# SCH_YDS-Charger-Daughter-Board_2022-05-2.net
KiCad netlist of a schematic drawn in EasyEDA
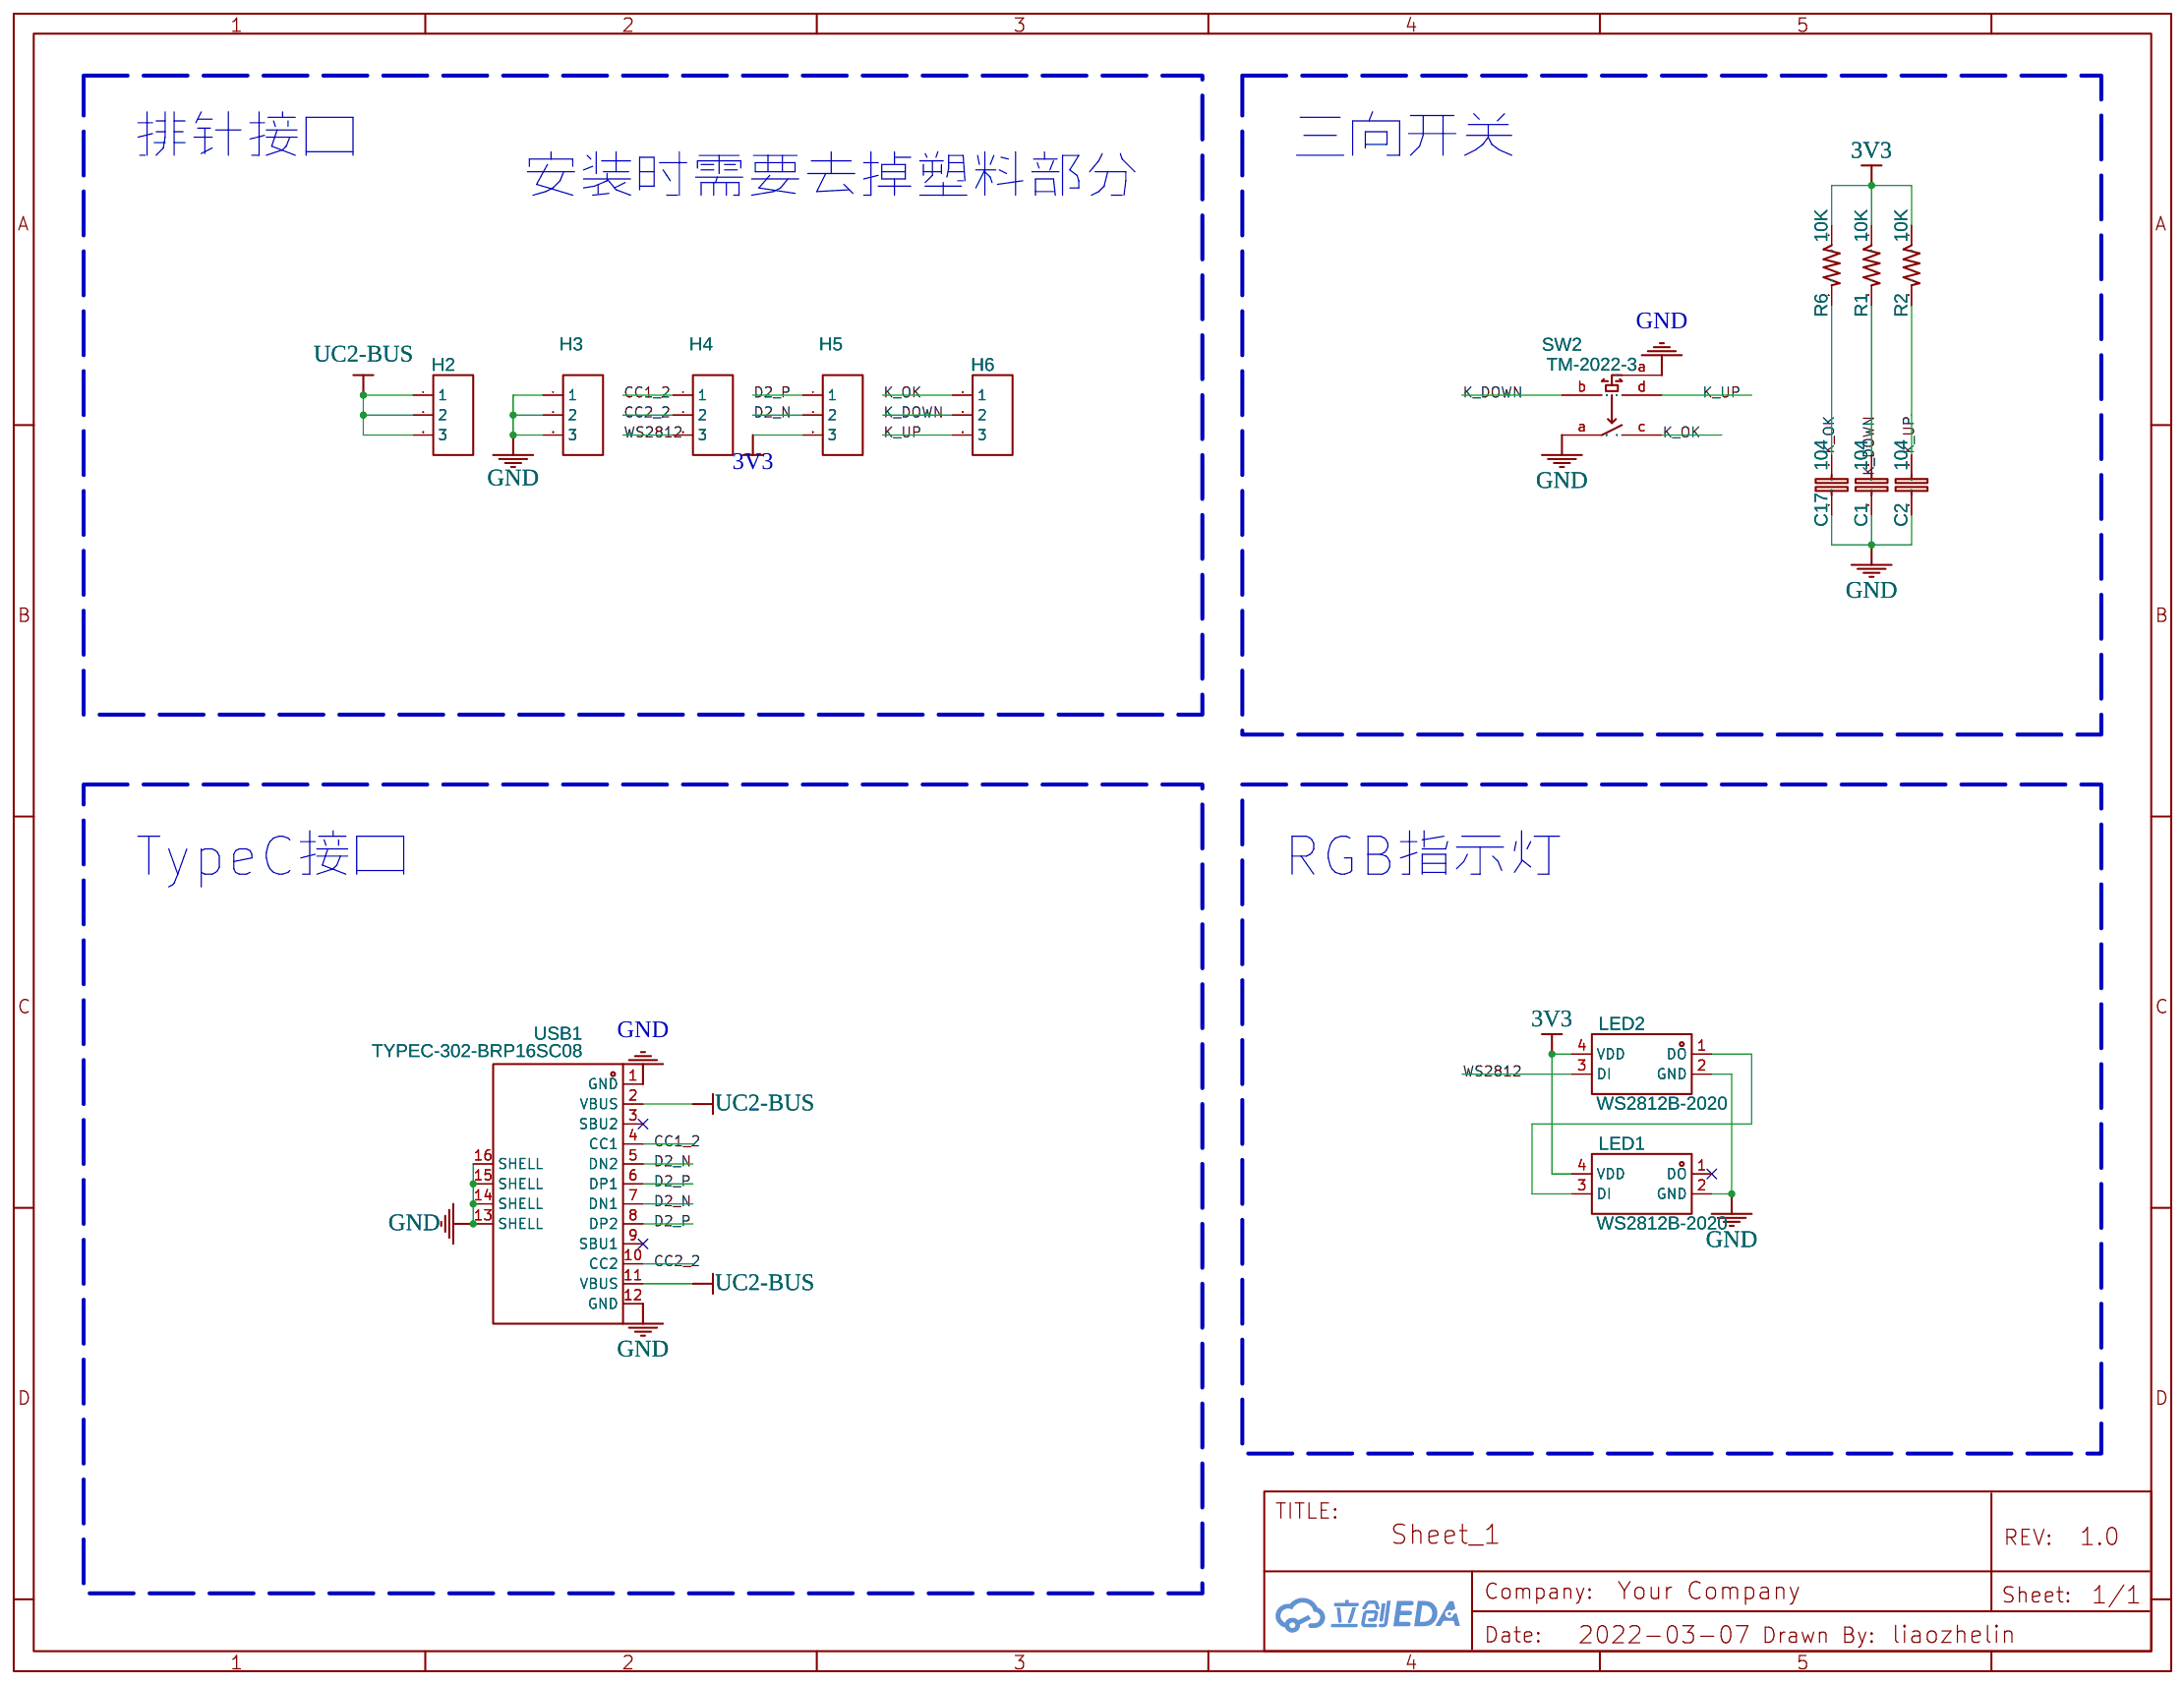
[diagram p0: schematic sheet]

(export (version "E")
  (design (tool "Eeschema 10.0.6"))
  (components
    (comp (ref "C1") (value "104") (libsource (lib "") (part "1.0PF-50V(-_+.25PF)(0603)")))
    (comp (ref "C2") (value "104") (libsource (lib "") (part "1.0PF-50V(-_+.25PF)(0603)")))
    (comp (ref "C17") (value "104") (libsource (lib "") (part "1.0PF-50V(-_+.25PF)(0603)")))
    (comp (ref "H2")
      (value "HDR-F-2.54_1x3")
      (fields (field (name "BOM_Supplier Part") "C146690"))
      (libsource (lib "") (part "HDR-F-2.54_1x3"))
    )
    (comp (ref "H3")
      (value "HDR-F-2.54_1x3")
      (fields (field (name "BOM_Supplier Part") "C146690"))
      (libsource (lib "") (part "HDR-F-2.54_1x3"))
    )
    (comp (ref "H4")
      (value "HDR-F-2.54_1x3")
      (fields (field (name "BOM_Supplier Part") "C146690"))
      (libsource (lib "") (part "HDR-F-2.54_1x3"))
    )
    (comp (ref "H5")
      (value "HDR-F-2.54_1x3")
      (fields (field (name "BOM_Supplier Part") "C146690"))
      (libsource (lib "") (part "HDR-F-2.54_1x3"))
    )
    (comp (ref "H6")
      (value "HDR-F-2.54_1x3")
      (fields (field (name "BOM_Supplier Part") "C146690"))
      (libsource (lib "") (part "HDR-F-2.54_1x3"))
    )
    (comp (ref "LED1")
      (value "WS2812B-2020")
      (fields (field (name "BOM_Supplier Part") "C965555"))
      (libsource (lib "") (part "WS2812B-2020"))
    )
    (comp (ref "LED2")
      (value "WS2812B-2020")
      (fields (field (name "BOM_Supplier Part") "C965555"))
      (libsource (lib "") (part "WS2812B-2020"))
    )
    (comp (ref "R1") (value "10K") (libsource (lib "") (part "1.2MOHMS-1_10W-1%(0603)")))
    (comp (ref "R2") (value "10K") (libsource (lib "") (part "1.2MOHMS-1_10W-1%(0603)")))
    (comp (ref "R6") (value "10K") (libsource (lib "") (part "1.2MOHMS-1_10W-1%(0603)")))
    (comp (ref "SW2")
      (value "TM-2022-3")
      (fields (field (name "BOM_Supplier Part") "C318952"))
      (libsource (lib "") (part "TM-2022-3"))
    )
    (comp (ref "USB1")
      (value "TYPEC-302-BRP16SC08")
      (fields (field (name "BOM_Supplier Part") "C2835312"))
      (libsource (lib "") (part "TYPEC-302-BRP16SC08"))
    )
  )
  (nets
    (net (code "1") (name "/CC1_2") (class "Default")
      (node (ref "H4") (pin "1") (pinfunction "1_1") (pintype "input"))
      (node (ref "USB1") (pin "4") (pinfunction "CC1_4") (pintype "unspecified"))
    )
    (net (code "2") (name "/CC2_2") (class "Default")
      (node (ref "H4") (pin "2") (pinfunction "2_2") (pintype "input"))
      (node (ref "USB1") (pin "10") (pinfunction "CC2_10") (pintype "unspecified"))
    )
    (net (code "3") (name "/D2_N") (class "Default")
      (node (ref "H5") (pin "2") (pinfunction "2_2") (pintype "input"))
      (node (ref "USB1") (pin "5") (pinfunction "DN2_5") (pintype "unspecified"))
      (node (ref "USB1") (pin "7") (pinfunction "DN1_7") (pintype "unspecified"))
    )
    (net (code "4") (name "/D2_P") (class "Default")
      (node (ref "H5") (pin "1") (pinfunction "1_1") (pintype "input"))
      (node (ref "USB1") (pin "6") (pinfunction "DP1_6") (pintype "unspecified"))
      (node (ref "USB1") (pin "8") (pinfunction "DP2_8") (pintype "unspecified"))
    )
    (net (code "5") (name "/K_DOWN") (class "Default")
      (node (ref "C1") (pin "1") (pinfunction "1_1") (pintype "unspecified"))
      (node (ref "H6") (pin "2") (pinfunction "2_2") (pintype "input"))
      (node (ref "R1") (pin "2") (pinfunction "2_2") (pintype "unspecified"))
      (node (ref "SW2") (pin "b") (pinfunction "b_b") (pintype "unspecified"))
    )
    (net (code "6") (name "/K_OK") (class "Default")
      (node (ref "C17") (pin "1") (pinfunction "1_1") (pintype "unspecified"))
      (node (ref "H6") (pin "1") (pinfunction "1_1") (pintype "input"))
      (node (ref "R6") (pin "2") (pinfunction "2_2") (pintype "unspecified"))
      (node (ref "SW2") (pin "c") (pinfunction "c_c") (pintype "unspecified"))
    )
    (net (code "7") (name "/K_UP") (class "Default")
      (node (ref "C2") (pin "1") (pinfunction "1_1") (pintype "unspecified"))
      (node (ref "H6") (pin "3") (pinfunction "3_3") (pintype "input"))
      (node (ref "R2") (pin "2") (pinfunction "2_2") (pintype "unspecified"))
      (node (ref "SW2") (pin "d") (pinfunction "d_d") (pintype "unspecified"))
    )
    (net (code "8") (name "/WS2812") (class "Default")
      (node (ref "H4") (pin "3") (pinfunction "3_3") (pintype "input"))
      (node (ref "LED2") (pin "3") (pinfunction "DI_3") (pintype "unspecified"))
    )
    (net (code "9") (name "3V3") (class "Default")
      (node (ref "H5") (pin "3") (pinfunction "3_3") (pintype "input"))
      (node (ref "LED1") (pin "4") (pinfunction "VDD_4") (pintype "unspecified"))
      (node (ref "LED2") (pin "4") (pinfunction "VDD_4") (pintype "unspecified"))
      (node (ref "R1") (pin "1") (pinfunction "1_1") (pintype "unspecified"))
      (node (ref "R2") (pin "1") (pinfunction "1_1") (pintype "unspecified"))
      (node (ref "R6") (pin "1") (pinfunction "1_1") (pintype "unspecified"))
    )
    (net (code "10") (name "GND") (class "Default")
      (node (ref "C1") (pin "2") (pinfunction "2_2") (pintype "unspecified"))
      (node (ref "C17") (pin "2") (pinfunction "2_2") (pintype "unspecified"))
      (node (ref "C2") (pin "2") (pinfunction "2_2") (pintype "unspecified"))
      (node (ref "H3") (pin "1") (pinfunction "1_1") (pintype "input"))
      (node (ref "H3") (pin "2") (pinfunction "2_2") (pintype "input"))
      (node (ref "H3") (pin "3") (pinfunction "3_3") (pintype "input"))
      (node (ref "LED1") (pin "2") (pinfunction "GND_2") (pintype "unspecified"))
      (node (ref "LED2") (pin "2") (pinfunction "GND_2") (pintype "unspecified"))
      (node (ref "SW2") (pin "a") (pinfunction "a_a") (pintype "unspecified"))
      (node (ref "USB1") (pin "1") (pinfunction "GND_1") (pintype "unspecified"))
      (node (ref "USB1") (pin "12") (pinfunction "GND_12") (pintype "unspecified"))
      (node (ref "USB1") (pin "13") (pinfunction "SHELL_13") (pintype "unspecified"))
      (node (ref "USB1") (pin "14") (pinfunction "SHELL_14") (pintype "unspecified"))
      (node (ref "USB1") (pin "15") (pinfunction "SHELL_15") (pintype "unspecified"))
      (node (ref "USB1") (pin "16") (pinfunction "SHELL_16") (pintype "unspecified"))
    )
    (net (code "11") (name "Net-(LED1-DI)") (class "Default")
      (node (ref "LED1") (pin "3") (pinfunction "DI_3") (pintype "unspecified"))
      (node (ref "LED2") (pin "1") (pinfunction "DO_1") (pintype "unspecified"))
    )
    (net (code "12") (name "UC2-BUS") (class "Default")
      (node (ref "H2") (pin "1") (pinfunction "1_1") (pintype "input"))
      (node (ref "H2") (pin "2") (pinfunction "2_2") (pintype "input"))
      (node (ref "H2") (pin "3") (pinfunction "3_3") (pintype "input"))
      (node (ref "USB1") (pin "11") (pinfunction "VBUS_11") (pintype "unspecified"))
      (node (ref "USB1") (pin "2") (pinfunction "VBUS_2") (pintype "unspecified"))
    )
    (net (code "13") (name "unconnected-(LED1-DO-Pad1)") (class "Default")
      (node (ref "LED1") (pin "1") (pinfunction "DO_1") (pintype "unspecified+no_connect"))
    )
    (net (code "14") (name "unconnected-(USB1-SBU1-Pad9)") (class "Default")
      (node (ref "USB1") (pin "9") (pinfunction "SBU1_9") (pintype "unspecified+no_connect"))
    )
    (net (code "15") (name "unconnected-(USB1-SBU2-Pad3)") (class "Default")
      (node (ref "USB1") (pin "3") (pinfunction "SBU2_3") (pintype "unspecified+no_connect"))
    )
  )
)
